# Thomas.net
KiCad netlist of a schematic drawn in EAGLE
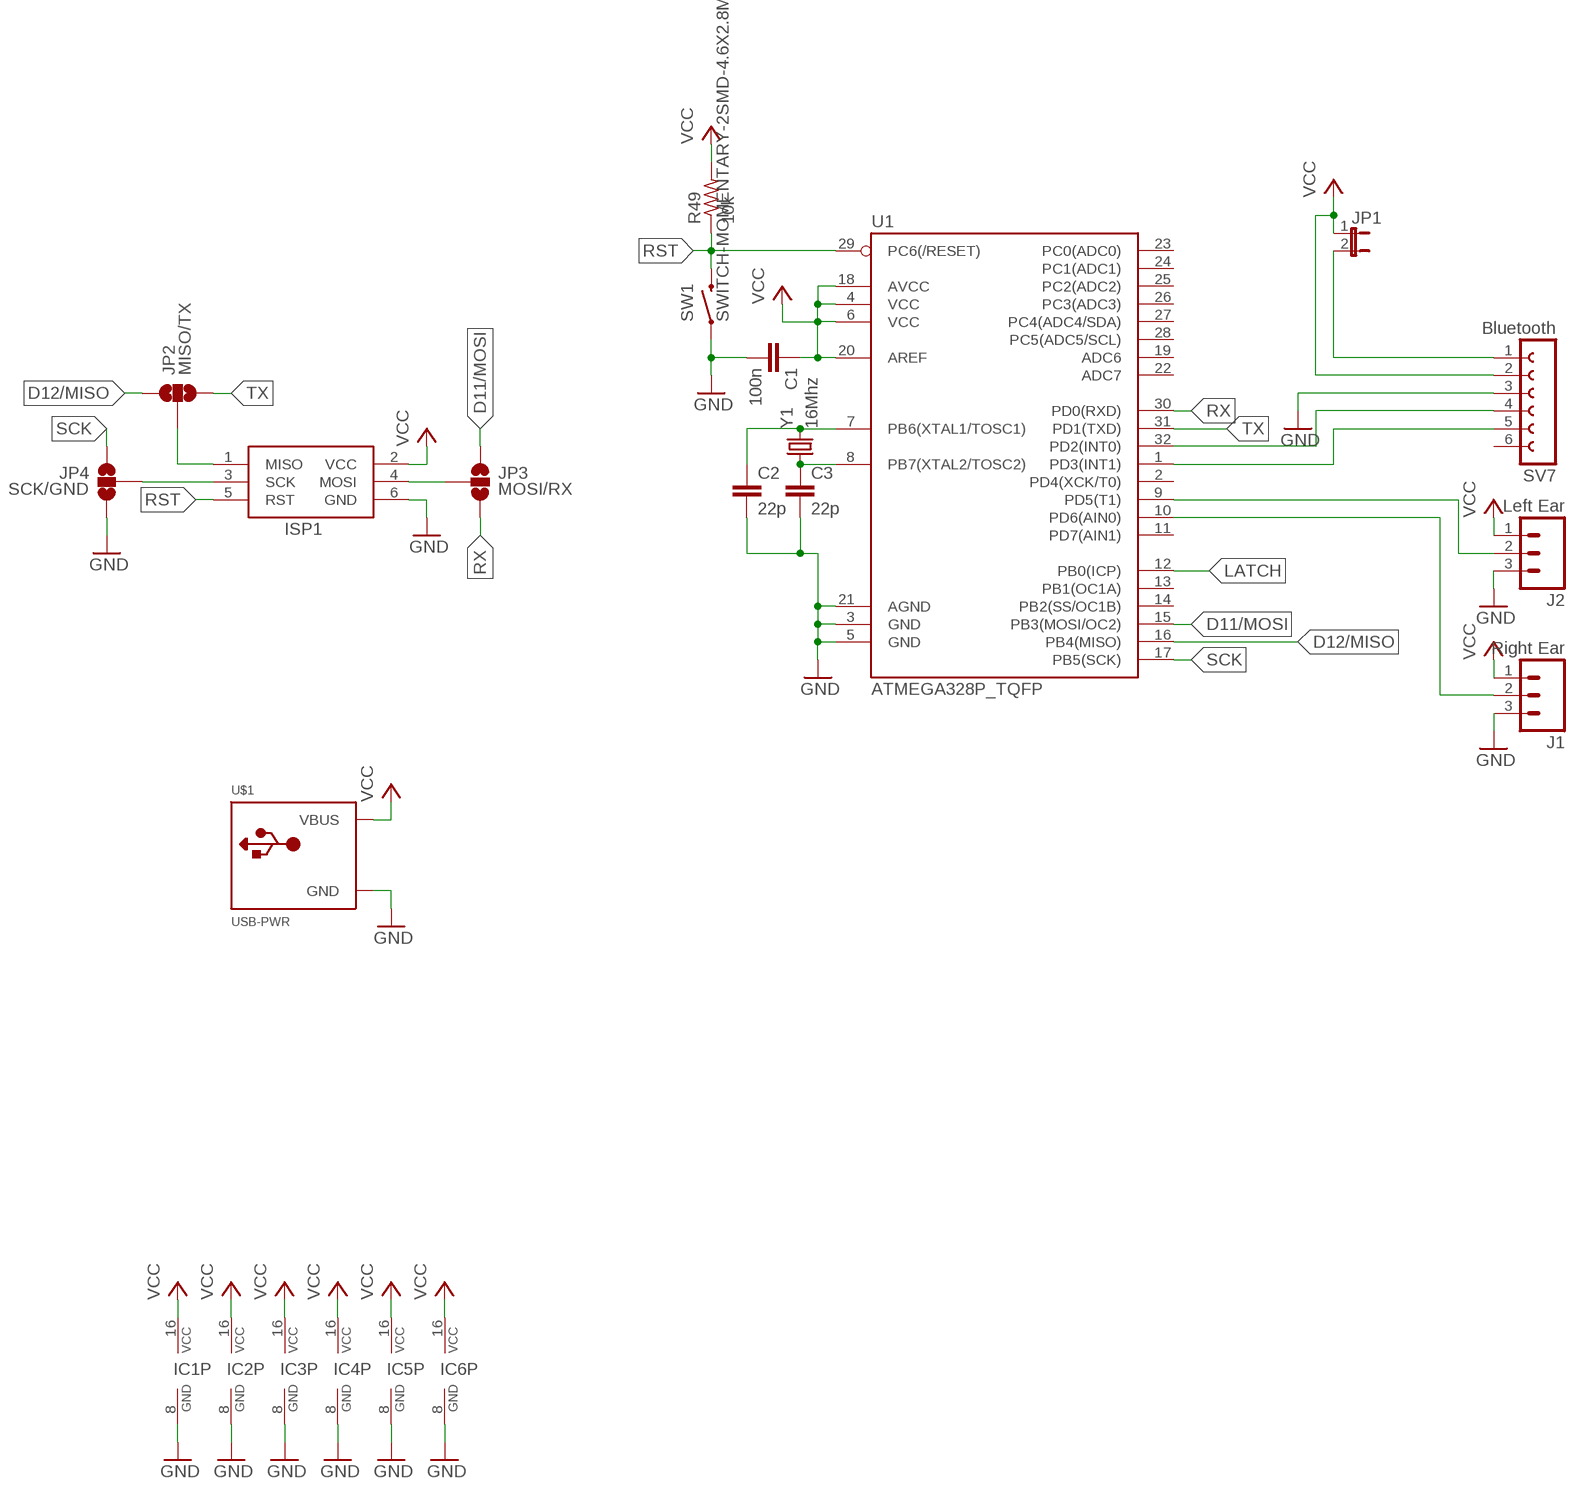
[diagram p0: schematic, sheet 1, part 1 of 2]
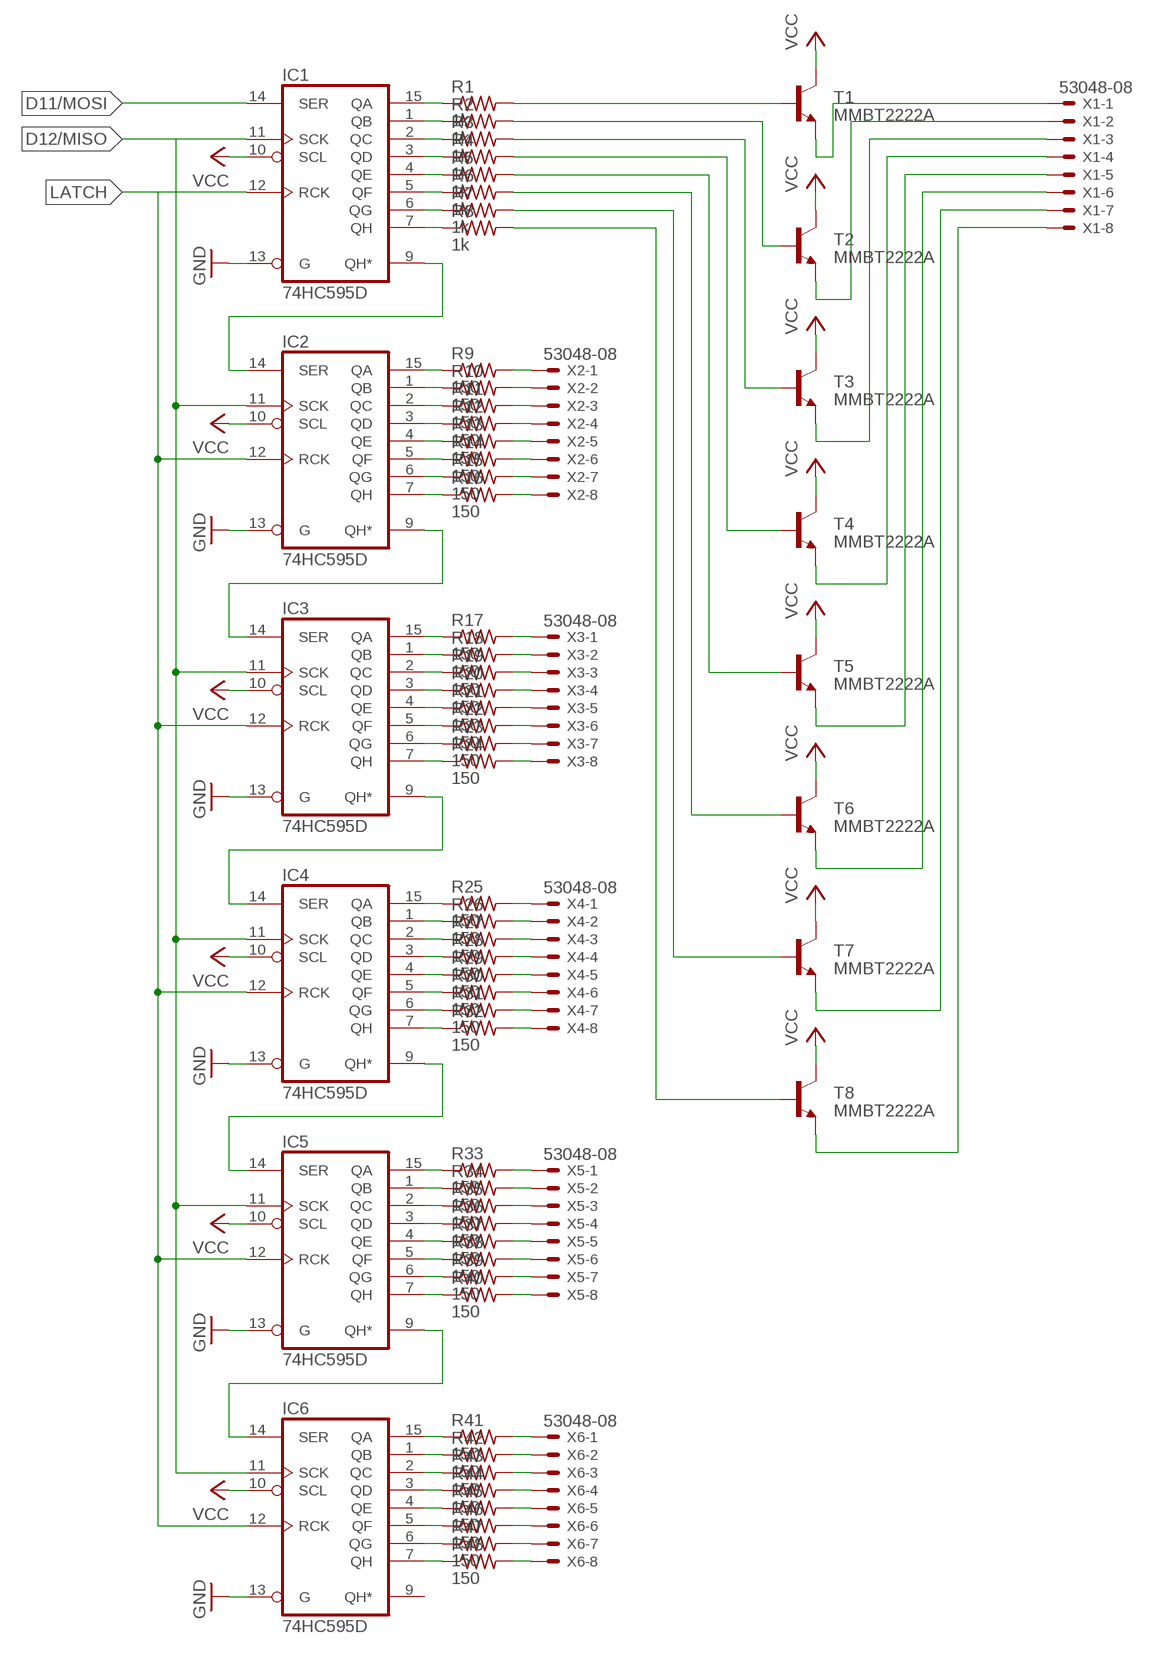
[diagram p1: schematic, sheet 1, part 2 of 2]

(export (version "E")
  (design (tool "Eeschema 10.0.6"))
  (components
    (comp (ref "C1")
      (value "100n")
      (footprint "eagle-import:C0805K")
      (libsource (lib "eagle-import") (part "C-EUC0805K"))
    )
    (comp (ref "C2")
      (value "22p")
      (footprint "eagle-import:C0805K")
      (libsource (lib "eagle-import") (part "C-EUC0805K"))
    )
    (comp (ref "C3")
      (value "22p")
      (footprint "eagle-import:C0805K")
      (libsource (lib "eagle-import") (part "C-EUC0805K"))
    )
    (comp (ref "IC1")
      (value "74HC595D")
      (footprint "eagle-import:SO16")
      (libsource (lib "eagle-import") (part "74595DHC"))
    )
    (comp (ref "IC2")
      (value "74HC595D")
      (footprint "eagle-import:SO16")
      (libsource (lib "eagle-import") (part "74595DHC"))
    )
    (comp (ref "IC3")
      (value "74HC595D")
      (footprint "eagle-import:SO16")
      (libsource (lib "eagle-import") (part "74595DHC"))
    )
    (comp (ref "IC4")
      (value "74HC595D")
      (footprint "eagle-import:SO16")
      (libsource (lib "eagle-import") (part "74595DHC"))
    )
    (comp (ref "IC5")
      (value "74HC595D")
      (footprint "eagle-import:SO16")
      (libsource (lib "eagle-import") (part "74595DHC"))
    )
    (comp (ref "IC6")
      (value "74HC595D")
      (footprint "eagle-import:SO16")
      (libsource (lib "eagle-import") (part "74595DHC"))
    )
    (comp (ref "ISP1")
      (value "AVRISP-6")
      (footprint "eagle-import:AVRISP")
      (libsource (lib "eagle-import") (part "AVRISP-6"))
    )
    (comp (ref "J1")
      (value "Right Ear")
      (footprint "eagle-import:1X03")
      (libsource (lib "eagle-import") (part "M03PTH"))
    )
    (comp (ref "J2")
      (value "Left Ear")
      (footprint "eagle-import:1X03")
      (libsource (lib "eagle-import") (part "M03PTH"))
    )
    (comp (ref "JP1")
      (value "JUMPER-2SMD-NC")
      (footprint "eagle-import:SJ_2S")
      (libsource (lib "eagle-import") (part "JUMPER-2SMD-NC"))
    )
    (comp (ref "JP2")
      (value "MISO/TX")
      (footprint "eagle-import:PAD-JUMPER-3-NO_YES_SILK")
      (libsource (lib "eagle-import") (part "JUMPER-PAD-3-NOYES_SILK"))
    )
    (comp (ref "JP3")
      (value "MOSI/RX")
      (footprint "eagle-import:PAD-JUMPER-3-NO_YES_SILK")
      (libsource (lib "eagle-import") (part "JUMPER-PAD-3-NOYES_SILK"))
    )
    (comp (ref "JP4")
      (value "SCK/GND")
      (footprint "eagle-import:PAD-JUMPER-3-NO_YES_SILK")
      (libsource (lib "eagle-import") (part "JUMPER-PAD-3-NOYES_SILK"))
    )
    (comp (ref "R1")
      (value "1k")
      (footprint "eagle-import:R0805")
      (libsource (lib "eagle-import") (part "R-US_R0805"))
    )
    (comp (ref "R2")
      (value "1k")
      (footprint "eagle-import:R0805")
      (libsource (lib "eagle-import") (part "R-US_R0805"))
    )
    (comp (ref "R3")
      (value "1k")
      (footprint "eagle-import:R0805")
      (libsource (lib "eagle-import") (part "R-US_R0805"))
    )
    (comp (ref "R4")
      (value "1k")
      (footprint "eagle-import:R0805")
      (libsource (lib "eagle-import") (part "R-US_R0805"))
    )
    (comp (ref "R5")
      (value "1k")
      (footprint "eagle-import:R0805")
      (libsource (lib "eagle-import") (part "R-US_R0805"))
    )
    (comp (ref "R6")
      (value "1k")
      (footprint "eagle-import:R0805")
      (libsource (lib "eagle-import") (part "R-US_R0805"))
    )
    (comp (ref "R7")
      (value "1k")
      (footprint "eagle-import:R0805")
      (libsource (lib "eagle-import") (part "R-US_R0805"))
    )
    (comp (ref "R8")
      (value "1k")
      (footprint "eagle-import:R0805")
      (libsource (lib "eagle-import") (part "R-US_R0805"))
    )
    (comp (ref "R9")
      (value "150")
      (footprint "eagle-import:R0805")
      (libsource (lib "eagle-import") (part "R-US_R0805"))
    )
    (comp (ref "R10")
      (value "150")
      (footprint "eagle-import:R0805")
      (libsource (lib "eagle-import") (part "R-US_R0805"))
    )
    (comp (ref "R11")
      (value "150")
      (footprint "eagle-import:R0805")
      (libsource (lib "eagle-import") (part "R-US_R0805"))
    )
    (comp (ref "R12")
      (value "150")
      (footprint "eagle-import:R0805")
      (libsource (lib "eagle-import") (part "R-US_R0805"))
    )
    (comp (ref "R13")
      (value "150")
      (footprint "eagle-import:R0805")
      (libsource (lib "eagle-import") (part "R-US_R0805"))
    )
    (comp (ref "R14")
      (value "150")
      (footprint "eagle-import:R0805")
      (libsource (lib "eagle-import") (part "R-US_R0805"))
    )
    (comp (ref "R15")
      (value "150")
      (footprint "eagle-import:R0805")
      (libsource (lib "eagle-import") (part "R-US_R0805"))
    )
    (comp (ref "R16")
      (value "150")
      (footprint "eagle-import:R0805")
      (libsource (lib "eagle-import") (part "R-US_R0805"))
    )
    (comp (ref "R17")
      (value "150")
      (footprint "eagle-import:R0805")
      (libsource (lib "eagle-import") (part "R-US_R0805"))
    )
    (comp (ref "R18")
      (value "150")
      (footprint "eagle-import:R0805")
      (libsource (lib "eagle-import") (part "R-US_R0805"))
    )
    (comp (ref "R19")
      (value "150")
      (footprint "eagle-import:R0805")
      (libsource (lib "eagle-import") (part "R-US_R0805"))
    )
    (comp (ref "R20")
      (value "150")
      (footprint "eagle-import:R0805")
      (libsource (lib "eagle-import") (part "R-US_R0805"))
    )
    (comp (ref "R21")
      (value "150")
      (footprint "eagle-import:R0805")
      (libsource (lib "eagle-import") (part "R-US_R0805"))
    )
    (comp (ref "R22")
      (value "150")
      (footprint "eagle-import:R0805")
      (libsource (lib "eagle-import") (part "R-US_R0805"))
    )
    (comp (ref "R23")
      (value "150")
      (footprint "eagle-import:R0805")
      (libsource (lib "eagle-import") (part "R-US_R0805"))
    )
    (comp (ref "R24")
      (value "150")
      (footprint "eagle-import:R0805")
      (libsource (lib "eagle-import") (part "R-US_R0805"))
    )
    (comp (ref "R25")
      (value "150")
      (footprint "eagle-import:R0805")
      (libsource (lib "eagle-import") (part "R-US_R0805"))
    )
    (comp (ref "R26")
      (value "150")
      (footprint "eagle-import:R0805")
      (libsource (lib "eagle-import") (part "R-US_R0805"))
    )
    (comp (ref "R27")
      (value "150")
      (footprint "eagle-import:R0805")
      (libsource (lib "eagle-import") (part "R-US_R0805"))
    )
    (comp (ref "R28")
      (value "150")
      (footprint "eagle-import:R0805")
      (libsource (lib "eagle-import") (part "R-US_R0805"))
    )
    (comp (ref "R29")
      (value "150")
      (footprint "eagle-import:R0805")
      (libsource (lib "eagle-import") (part "R-US_R0805"))
    )
    (comp (ref "R30")
      (value "150")
      (footprint "eagle-import:R0805")
      (libsource (lib "eagle-import") (part "R-US_R0805"))
    )
    (comp (ref "R31")
      (value "150")
      (footprint "eagle-import:R0805")
      (libsource (lib "eagle-import") (part "R-US_R0805"))
    )
    (comp (ref "R32")
      (value "150")
      (footprint "eagle-import:R0805")
      (libsource (lib "eagle-import") (part "R-US_R0805"))
    )
    (comp (ref "R33")
      (value "150")
      (footprint "eagle-import:R0805")
      (libsource (lib "eagle-import") (part "R-US_R0805"))
    )
    (comp (ref "R34")
      (value "150")
      (footprint "eagle-import:R0805")
      (libsource (lib "eagle-import") (part "R-US_R0805"))
    )
    (comp (ref "R35")
      (value "150")
      (footprint "eagle-import:R0805")
      (libsource (lib "eagle-import") (part "R-US_R0805"))
    )
    (comp (ref "R36")
      (value "150")
      (footprint "eagle-import:R0805")
      (libsource (lib "eagle-import") (part "R-US_R0805"))
    )
    (comp (ref "R37")
      (value "150")
      (footprint "eagle-import:R0805")
      (libsource (lib "eagle-import") (part "R-US_R0805"))
    )
    (comp (ref "R38")
      (value "150")
      (footprint "eagle-import:R0805")
      (libsource (lib "eagle-import") (part "R-US_R0805"))
    )
    (comp (ref "R39")
      (value "150")
      (footprint "eagle-import:R0805")
      (libsource (lib "eagle-import") (part "R-US_R0805"))
    )
    (comp (ref "R40")
      (value "150")
      (footprint "eagle-import:R0805")
      (libsource (lib "eagle-import") (part "R-US_R0805"))
    )
    (comp (ref "R41")
      (value "150")
      (footprint "eagle-import:R0805")
      (libsource (lib "eagle-import") (part "R-US_R0805"))
    )
    (comp (ref "R42")
      (value "150")
      (footprint "eagle-import:R0805")
      (libsource (lib "eagle-import") (part "R-US_R0805"))
    )
    (comp (ref "R43")
      (value "150")
      (footprint "eagle-import:R0805")
      (libsource (lib "eagle-import") (part "R-US_R0805"))
    )
    (comp (ref "R44")
      (value "150")
      (footprint "eagle-import:R0805")
      (libsource (lib "eagle-import") (part "R-US_R0805"))
    )
    (comp (ref "R45")
      (value "150")
      (footprint "eagle-import:R0805")
      (libsource (lib "eagle-import") (part "R-US_R0805"))
    )
    (comp (ref "R46")
      (value "150")
      (footprint "eagle-import:R0805")
      (libsource (lib "eagle-import") (part "R-US_R0805"))
    )
    (comp (ref "R47")
      (value "150")
      (footprint "eagle-import:R0805")
      (libsource (lib "eagle-import") (part "R-US_R0805"))
    )
    (comp (ref "R48")
      (value "150")
      (footprint "eagle-import:R0805")
      (libsource (lib "eagle-import") (part "R-US_R0805"))
    )
    (comp (ref "R49")
      (value "10k")
      (footprint "eagle-import:R0805")
      (libsource (lib "eagle-import") (part "R-US_R0805"))
    )
    (comp (ref "SV7")
      (value "Bluetooth")
      (footprint "eagle-import:FE06")
      (libsource (lib "eagle-import") (part "FE06-1"))
    )
    (comp (ref "SW1")
      (value "SWITCH-MOMENTARY-2SMD-4.6X2.8MM")
      (footprint "eagle-import:TACTILE_SWITCH_SMD_4.6X2.8MM")
      (libsource (lib "eagle-import") (part "SWITCH-MOMENTARY-2SMD-4.6X2.8MM"))
    )
    (comp (ref "T1")
      (value "MMBT2222A")
      (footprint "eagle-import:SOT23-3")
      (libsource (lib "eagle-import") (part "TRANSISTOR_NPNMMBT2222A"))
    )
    (comp (ref "T2")
      (value "MMBT2222A")
      (footprint "eagle-import:SOT23-3")
      (libsource (lib "eagle-import") (part "TRANSISTOR_NPNMMBT2222A"))
    )
    (comp (ref "T3")
      (value "MMBT2222A")
      (footprint "eagle-import:SOT23-3")
      (libsource (lib "eagle-import") (part "TRANSISTOR_NPNMMBT2222A"))
    )
    (comp (ref "T4")
      (value "MMBT2222A")
      (footprint "eagle-import:SOT23-3")
      (libsource (lib "eagle-import") (part "TRANSISTOR_NPNMMBT2222A"))
    )
    (comp (ref "T5")
      (value "MMBT2222A")
      (footprint "eagle-import:SOT23-3")
      (libsource (lib "eagle-import") (part "TRANSISTOR_NPNMMBT2222A"))
    )
    (comp (ref "T6")
      (value "MMBT2222A")
      (footprint "eagle-import:SOT23-3")
      (libsource (lib "eagle-import") (part "TRANSISTOR_NPNMMBT2222A"))
    )
    (comp (ref "T7")
      (value "MMBT2222A")
      (footprint "eagle-import:SOT23-3")
      (libsource (lib "eagle-import") (part "TRANSISTOR_NPNMMBT2222A"))
    )
    (comp (ref "T8")
      (value "MMBT2222A")
      (footprint "eagle-import:SOT23-3")
      (libsource (lib "eagle-import") (part "TRANSISTOR_NPNMMBT2222A"))
    )
    (comp (ref "U$1")
      (value "USB-PWR")
      (footprint "eagle-import:USB-MINIB-THM-MOLEX-PWRONLY")
      (libsource (lib "eagle-import") (part "USB-PWR"))
    )
    (comp (ref "U1")
      (value "ATMEGA328P_TQFP")
      (footprint "eagle-import:TQFP32-08")
      (libsource (lib "eagle-import") (part "ATMEGA328P_TQFP"))
    )
    (comp (ref "X1")
      (value "53048-08")
      (footprint "eagle-import:53048-08")
      (fields (field (name "MF") "WALDOM/MOLEX") (field (name "MPN") "53048-0810"))
      (libsource (lib "eagle-import") (part "53?-08048"))
    )
    (comp (ref "X2")
      (value "53048-08")
      (footprint "eagle-import:53048-08")
      (fields (field (name "MF") "WALDOM/MOLEX") (field (name "MPN") "53048-0810"))
      (libsource (lib "eagle-import") (part "53?-08048"))
    )
    (comp (ref "X3")
      (value "53048-08")
      (footprint "eagle-import:53048-08")
      (fields (field (name "MF") "WALDOM/MOLEX") (field (name "MPN") "53048-0810"))
      (libsource (lib "eagle-import") (part "53?-08048"))
    )
    (comp (ref "X4")
      (value "53048-08")
      (footprint "eagle-import:53048-08")
      (fields (field (name "MF") "WALDOM/MOLEX") (field (name "MPN") "53048-0810"))
      (libsource (lib "eagle-import") (part "53?-08048"))
    )
    (comp (ref "X5")
      (value "53048-08")
      (footprint "eagle-import:53048-08")
      (fields (field (name "MF") "WALDOM/MOLEX") (field (name "MPN") "53048-0810"))
      (libsource (lib "eagle-import") (part "53?-08048"))
    )
    (comp (ref "X6")
      (value "53048-08")
      (footprint "eagle-import:53048-08")
      (fields (field (name "MF") "WALDOM/MOLEX") (field (name "MPN") "53048-0810"))
      (libsource (lib "eagle-import") (part "53?-08048"))
    )
    (comp (ref "Y1")
      (value "16Mhz")
      (footprint "eagle-import:CRYSTAL-SMD-3.2X1.5MM")
      (libsource (lib "eagle-import") (part "CRYSTAL3.2X1.5MM"))
    )
  )
  (nets
    (net (code "1") (name "D11{slash}MOSI") (class "Default")
      (node (ref "IC1") (pin "14") (pinfunction "SER_14") (pintype "input"))
      (node (ref "JP3") (pin "1") (pinfunction "1_1") (pintype "passive"))
      (node (ref "U1") (pin "15") (pinfunction "PB3(MOSI/OC2)_15") (pintype "bidirectional"))
    )
    (net (code "2") (name "D12{slash}MISO") (class "Default")
      (node (ref "IC1") (pin "11") (pinfunction "SCK_11") (pintype "input"))
      (node (ref "IC2") (pin "11") (pinfunction "SCK_11") (pintype "input"))
      (node (ref "IC3") (pin "11") (pinfunction "SCK_11") (pintype "input"))
      (node (ref "IC4") (pin "11") (pinfunction "SCK_11") (pintype "input"))
      (node (ref "IC5") (pin "11") (pinfunction "SCK_11") (pintype "input"))
      (node (ref "IC6") (pin "11") (pinfunction "SCK_11") (pintype "input"))
      (node (ref "JP2") (pin "1") (pinfunction "1_1") (pintype "passive"))
      (node (ref "U1") (pin "16") (pinfunction "PB4(MISO)_16") (pintype "bidirectional"))
    )
    (net (code "3") (name "GND") (class "Default")
      (node (ref "C1") (pin "2") (pinfunction "2_2") (pintype "passive"))
      (node (ref "C2") (pin "2") (pinfunction "2_2") (pintype "passive"))
      (node (ref "C3") (pin "2") (pinfunction "2_2") (pintype "passive"))
      (node (ref "IC1") (pin "13") (pinfunction "G_13") (pintype "input"))
      (node (ref "IC1") (pin "8") (pinfunction "GND_8") (pintype "power_in"))
      (node (ref "IC2") (pin "13") (pinfunction "G_13") (pintype "input"))
      (node (ref "IC2") (pin "8") (pinfunction "GND_8") (pintype "power_in"))
      (node (ref "IC3") (pin "13") (pinfunction "G_13") (pintype "input"))
      (node (ref "IC3") (pin "8") (pinfunction "GND_8") (pintype "power_in"))
      (node (ref "IC4") (pin "13") (pinfunction "G_13") (pintype "input"))
      (node (ref "IC4") (pin "8") (pinfunction "GND_8") (pintype "power_in"))
      (node (ref "IC5") (pin "13") (pinfunction "G_13") (pintype "input"))
      (node (ref "IC5") (pin "8") (pinfunction "GND_8") (pintype "power_in"))
      (node (ref "IC6") (pin "13") (pinfunction "G_13") (pintype "input"))
      (node (ref "IC6") (pin "8") (pinfunction "GND_8") (pintype "power_in"))
      (node (ref "ISP1") (pin "6") (pinfunction "GND_6") (pintype "power_in"))
      (node (ref "J1") (pin "3") (pinfunction "3_3") (pintype "passive"))
      (node (ref "J2") (pin "3") (pinfunction "3_3") (pintype "passive"))
      (node (ref "JP4") (pin "3") (pinfunction "3_3") (pintype "passive"))
      (node (ref "SV7") (pin "3") (pinfunction "3_3") (pintype "passive"))
      (node (ref "SW1") (pin "1") (pinfunction "1_1") (pintype "passive"))
      (node (ref "SW1") (pin "2") (pinfunction "1_2") (pintype "passive"))
      (node (ref "U$1") (pin "GND") (pinfunction "GND_GND") (pintype "power_in"))
      (node (ref "U1") (pin "21") (pinfunction "AGND_21") (pintype "bidirectional"))
      (node (ref "U1") (pin "3") (pinfunction "GND_3") (pintype "bidirectional"))
      (node (ref "U1") (pin "5") (pinfunction "GND_5") (pintype "bidirectional"))
    )
    (net (code "4") (name "LATCH") (class "Default")
      (node (ref "IC1") (pin "12") (pinfunction "RCK_12") (pintype "input"))
      (node (ref "IC2") (pin "12") (pinfunction "RCK_12") (pintype "input"))
      (node (ref "IC3") (pin "12") (pinfunction "RCK_12") (pintype "input"))
      (node (ref "IC4") (pin "12") (pinfunction "RCK_12") (pintype "input"))
      (node (ref "IC5") (pin "12") (pinfunction "RCK_12") (pintype "input"))
      (node (ref "IC6") (pin "12") (pinfunction "RCK_12") (pintype "input"))
      (node (ref "U1") (pin "12") (pinfunction "PB0(ICP)_12") (pintype "bidirectional"))
    )
    (net (code "5") (name "Net-(IC1A-QA)") (class "Default")
      (node (ref "IC1") (pin "15") (pinfunction "QA_15") (pintype "tri_state"))
      (node (ref "R1") (pin "1") (pinfunction "1_1") (pintype "passive"))
    )
    (net (code "6") (name "Net-(IC1A-QB)") (class "Default")
      (node (ref "IC1") (pin "1") (pinfunction "QB_1") (pintype "tri_state"))
      (node (ref "R2") (pin "1") (pinfunction "1_1") (pintype "passive"))
    )
    (net (code "7") (name "Net-(IC1A-QC)") (class "Default")
      (node (ref "IC1") (pin "2") (pinfunction "QC_2") (pintype "tri_state"))
      (node (ref "R3") (pin "1") (pinfunction "1_1") (pintype "passive"))
    )
    (net (code "8") (name "Net-(IC1A-QD)") (class "Default")
      (node (ref "IC1") (pin "3") (pinfunction "QD_3") (pintype "tri_state"))
      (node (ref "R4") (pin "1") (pinfunction "1_1") (pintype "passive"))
    )
    (net (code "9") (name "Net-(IC1A-QE)") (class "Default")
      (node (ref "IC1") (pin "4") (pinfunction "QE_4") (pintype "tri_state"))
      (node (ref "R5") (pin "1") (pinfunction "1_1") (pintype "passive"))
    )
    (net (code "10") (name "Net-(IC1A-QF)") (class "Default")
      (node (ref "IC1") (pin "5") (pinfunction "QF_5") (pintype "tri_state"))
      (node (ref "R6") (pin "1") (pinfunction "1_1") (pintype "passive"))
    )
    (net (code "11") (name "Net-(IC1A-QG)") (class "Default")
      (node (ref "IC1") (pin "6") (pinfunction "QG_6") (pintype "tri_state"))
      (node (ref "R7") (pin "1") (pinfunction "1_1") (pintype "passive"))
    )
    (net (code "12") (name "Net-(IC1A-QH)") (class "Default")
      (node (ref "IC1") (pin "7") (pinfunction "QH_7") (pintype "tri_state"))
      (node (ref "R8") (pin "1") (pinfunction "1_1") (pintype "passive"))
    )
    (net (code "13") (name "Net-(IC1A-QH*)") (class "Default")
      (node (ref "IC1") (pin "9") (pinfunction "QH*_9") (pintype "tri_state"))
      (node (ref "IC2") (pin "14") (pinfunction "SER_14") (pintype "input"))
    )
    (net (code "14") (name "Net-(IC2A-QA)") (class "Default")
      (node (ref "IC2") (pin "15") (pinfunction "QA_15") (pintype "tri_state"))
      (node (ref "R9") (pin "1") (pinfunction "1_1") (pintype "passive"))
    )
    (net (code "15") (name "Net-(IC2A-QB)") (class "Default")
      (node (ref "IC2") (pin "1") (pinfunction "QB_1") (pintype "tri_state"))
      (node (ref "R10") (pin "1") (pinfunction "1_1") (pintype "passive"))
    )
    (net (code "16") (name "Net-(IC2A-QC)") (class "Default")
      (node (ref "IC2") (pin "2") (pinfunction "QC_2") (pintype "tri_state"))
      (node (ref "R11") (pin "1") (pinfunction "1_1") (pintype "passive"))
    )
    (net (code "17") (name "Net-(IC2A-QD)") (class "Default")
      (node (ref "IC2") (pin "3") (pinfunction "QD_3") (pintype "tri_state"))
      (node (ref "R12") (pin "1") (pinfunction "1_1") (pintype "passive"))
    )
    (net (code "18") (name "Net-(IC2A-QE)") (class "Default")
      (node (ref "IC2") (pin "4") (pinfunction "QE_4") (pintype "tri_state"))
      (node (ref "R13") (pin "1") (pinfunction "1_1") (pintype "passive"))
    )
    (net (code "19") (name "Net-(IC2A-QF)") (class "Default")
      (node (ref "IC2") (pin "5") (pinfunction "QF_5") (pintype "tri_state"))
      (node (ref "R14") (pin "1") (pinfunction "1_1") (pintype "passive"))
    )
    (net (code "20") (name "Net-(IC2A-QG)") (class "Default")
      (node (ref "IC2") (pin "6") (pinfunction "QG_6") (pintype "tri_state"))
      (node (ref "R15") (pin "1") (pinfunction "1_1") (pintype "passive"))
    )
    (net (code "21") (name "Net-(IC2A-QH)") (class "Default")
      (node (ref "IC2") (pin "7") (pinfunction "QH_7") (pintype "tri_state"))
      (node (ref "R16") (pin "1") (pinfunction "1_1") (pintype "passive"))
    )
    (net (code "22") (name "Net-(IC2A-QH*)") (class "Default")
      (node (ref "IC2") (pin "9") (pinfunction "QH*_9") (pintype "tri_state"))
      (node (ref "IC3") (pin "14") (pinfunction "SER_14") (pintype "input"))
    )
    (net (code "23") (name "Net-(IC3A-QA)") (class "Default")
      (node (ref "IC3") (pin "15") (pinfunction "QA_15") (pintype "tri_state"))
      (node (ref "R17") (pin "1") (pinfunction "1_1") (pintype "passive"))
    )
    (net (code "24") (name "Net-(IC3A-QB)") (class "Default")
      (node (ref "IC3") (pin "1") (pinfunction "QB_1") (pintype "tri_state"))
      (node (ref "R18") (pin "1") (pinfunction "1_1") (pintype "passive"))
    )
    (net (code "25") (name "Net-(IC3A-QC)") (class "Default")
      (node (ref "IC3") (pin "2") (pinfunction "QC_2") (pintype "tri_state"))
      (node (ref "R19") (pin "1") (pinfunction "1_1") (pintype "passive"))
    )
    (net (code "26") (name "Net-(IC3A-QD)") (class "Default")
      (node (ref "IC3") (pin "3") (pinfunction "QD_3") (pintype "tri_state"))
      (node (ref "R20") (pin "1") (pinfunction "1_1") (pintype "passive"))
    )
    (net (code "27") (name "Net-(IC3A-QE)") (class "Default")
      (node (ref "IC3") (pin "4") (pinfunction "QE_4") (pintype "tri_state"))
      (node (ref "R21") (pin "1") (pinfunction "1_1") (pintype "passive"))
    )
    (net (code "28") (name "Net-(IC3A-QF)") (class "Default")
      (node (ref "IC3") (pin "5") (pinfunction "QF_5") (pintype "tri_state"))
      (node (ref "R22") (pin "1") (pinfunction "1_1") (pintype "passive"))
    )
    (net (code "29") (name "Net-(IC3A-QG)") (class "Default")
      (node (ref "IC3") (pin "6") (pinfunction "QG_6") (pintype "tri_state"))
      (node (ref "R23") (pin "1") (pinfunction "1_1") (pintype "passive"))
    )
    (net (code "30") (name "Net-(IC3A-QH)") (class "Default")
      (node (ref "IC3") (pin "7") (pinfunction "QH_7") (pintype "tri_state"))
      (node (ref "R24") (pin "1") (pinfunction "1_1") (pintype "passive"))
    )
    (net (code "31") (name "Net-(IC3A-QH*)") (class "Default")
      (node (ref "IC3") (pin "9") (pinfunction "QH*_9") (pintype "tri_state"))
      (node (ref "IC4") (pin "14") (pinfunction "SER_14") (pintype "input"))
    )
    (net (code "32") (name "Net-(IC4A-QA)") (class "Default")
      (node (ref "IC4") (pin "15") (pinfunction "QA_15") (pintype "tri_state"))
      (node (ref "R25") (pin "1") (pinfunction "1_1") (pintype "passive"))
    )
    (net (code "33") (name "Net-(IC4A-QB)") (class "Default")
      (node (ref "IC4") (pin "1") (pinfunction "QB_1") (pintype "tri_state"))
      (node (ref "R26") (pin "1") (pinfunction "1_1") (pintype "passive"))
    )
    (net (code "34") (name "Net-(IC4A-QC)") (class "Default")
      (node (ref "IC4") (pin "2") (pinfunction "QC_2") (pintype "tri_state"))
      (node (ref "R27") (pin "1") (pinfunction "1_1") (pintype "passive"))
    )
    (net (code "35") (name "Net-(IC4A-QD)") (class "Default")
      (node (ref "IC4") (pin "3") (pinfunction "QD_3") (pintype "tri_state"))
      (node (ref "R28") (pin "1") (pinfunction "1_1") (pintype "passive"))
    )
    (net (code "36") (name "Net-(IC4A-QE)") (class "Default")
      (node (ref "IC4") (pin "4") (pinfunction "QE_4") (pintype "tri_state"))
      (node (ref "R29") (pin "1") (pinfunction "1_1") (pintype "passive"))
    )
    (net (code "37") (name "Net-(IC4A-QF)") (class "Default")
      (node (ref "IC4") (pin "5") (pinfunction "QF_5") (pintype "tri_state"))
      (node (ref "R30") (pin "1") (pinfunction "1_1") (pintype "passive"))
    )
    (net (code "38") (name "Net-(IC4A-QG)") (class "Default")
      (node (ref "IC4") (pin "6") (pinfunction "QG_6") (pintype "tri_state"))
      (node (ref "R31") (pin "1") (pinfunction "1_1") (pintype "passive"))
    )
    (net (code "39") (name "Net-(IC4A-QH)") (class "Default")
      (node (ref "IC4") (pin "7") (pinfunction "QH_7") (pintype "tri_state"))
      (node (ref "R32") (pin "1") (pinfunction "1_1") (pintype "passive"))
    )
    (net (code "40") (name "Net-(IC4A-QH*)") (class "Default")
      (node (ref "IC4") (pin "9") (pinfunction "QH*_9") (pintype "tri_state"))
      (node (ref "IC5") (pin "14") (pinfunction "SER_14") (pintype "input"))
    )
    (net (code "41") (name "Net-(IC5A-QA)") (class "Default")
      (node (ref "IC5") (pin "15") (pinfunction "QA_15") (pintype "tri_state"))
      (node (ref "R33") (pin "1") (pinfunction "1_1") (pintype "passive"))
    )
    (net (code "42") (name "Net-(IC5A-QB)") (class "Default")
      (node (ref "IC5") (pin "1") (pinfunction "QB_1") (pintype "tri_state"))
      (node (ref "R34") (pin "1") (pinfunction "1_1") (pintype "passive"))
    )
    (net (code "43") (name "Net-(IC5A-QC)") (class "Default")
      (node (ref "IC5") (pin "2") (pinfunction "QC_2") (pintype "tri_state"))
      (node (ref "R35") (pin "1") (pinfunction "1_1") (pintype "passive"))
    )
    (net (code "44") (name "Net-(IC5A-QD)") (class "Default")
      (node (ref "IC5") (pin "3") (pinfunction "QD_3") (pintype "tri_state"))
      (node (ref "R36") (pin "1") (pinfunction "1_1") (pintype "passive"))
    )
    (net (code "45") (name "Net-(IC5A-QE)") (class "Default")
      (node (ref "IC5") (pin "4") (pinfunction "QE_4") (pintype "tri_state"))
      (node (ref "R37") (pin "1") (pinfunction "1_1") (pintype "passive"))
    )
    (net (code "46") (name "Net-(IC5A-QF)") (class "Default")
      (node (ref "IC5") (pin "5") (pinfunction "QF_5") (pintype "tri_state"))
      (node (ref "R38") (pin "1") (pinfunction "1_1") (pintype "passive"))
    )
    (net (code "47") (name "Net-(IC5A-QG)") (class "Default")
      (node (ref "IC5") (pin "6") (pinfunction "QG_6") (pintype "tri_state"))
      (node (ref "R39") (pin "1") (pinfunction "1_1") (pintype "passive"))
    )
    (net (code "48") (name "Net-(IC5A-QH)") (class "Default")
      (node (ref "IC5") (pin "7") (pinfunction "QH_7") (pintype "tri_state"))
      (node (ref "R40") (pin "1") (pinfunction "1_1") (pintype "passive"))
    )
    (net (code "49") (name "Net-(IC5A-QH*)") (class "Default")
      (node (ref "IC5") (pin "9") (pinfunction "QH*_9") (pintype "tri_state"))
      (node (ref "IC6") (pin "14") (pinfunction "SER_14") (pintype "input"))
    )
    (net (code "50") (name "Net-(IC6A-QA)") (class "Default")
      (node (ref "IC6") (pin "15") (pinfunction "QA_15") (pintype "tri_state"))
      (node (ref "R41") (pin "1") (pinfunction "1_1") (pintype "passive"))
    )
    (net (code "51") (name "Net-(IC6A-QB)") (class "Default")
      (node (ref "IC6") (pin "1") (pinfunction "QB_1") (pintype "tri_state"))
      (node (ref "R42") (pin "1") (pinfunction "1_1") (pintype "passive"))
    )
    (net (code "52") (name "Net-(IC6A-QC)") (class "Default")
      (node (ref "IC6") (pin "2") (pinfunction "QC_2") (pintype "tri_state"))
      (node (ref "R43") (pin "1") (pinfunction "1_1") (pintype "passive"))
    )
    (net (code "53") (name "Net-(IC6A-QD)") (class "Default")
      (node (ref "IC6") (pin "3") (pinfunction "QD_3") (pintype "tri_state"))
      (node (ref "R44") (pin "1") (pinfunction "1_1") (pintype "passive"))
    )
    (net (code "54") (name "Net-(IC6A-QE)") (class "Default")
      (node (ref "IC6") (pin "4") (pinfunction "QE_4") (pintype "tri_state"))
      (node (ref "R45") (pin "1") (pinfunction "1_1") (pintype "passive"))
    )
    (net (code "55") (name "Net-(IC6A-QF)") (class "Default")
      (node (ref "IC6") (pin "5") (pinfunction "QF_5") (pintype "tri_state"))
      (node (ref "R46") (pin "1") (pinfunction "1_1") (pintype "passive"))
    )
    (net (code "56") (name "Net-(IC6A-QG)") (class "Default")
      (node (ref "IC6") (pin "6") (pinfunction "QG_6") (pintype "tri_state"))
      (node (ref "R47") (pin "1") (pinfunction "1_1") (pintype "passive"))
    )
    (net (code "57") (name "Net-(IC6A-QH)") (class "Default")
      (node (ref "IC6") (pin "7") (pinfunction "QH_7") (pintype "tri_state"))
      (node (ref "R48") (pin "1") (pinfunction "1_1") (pintype "passive"))
    )
    (net (code "58") (name "Net-(ISP1-MISO)") (class "Default")
      (node (ref "ISP1") (pin "1") (pinfunction "MISO_1") (pintype "input"))
      (node (ref "JP2") (pin "2") (pinfunction "2_2") (pintype "passive"))
    )
    (net (code "59") (name "Net-(ISP1-MOSI)") (class "Default")
      (node (ref "ISP1") (pin "4") (pinfunction "MOSI_4") (pintype "output"))
      (node (ref "JP3") (pin "2") (pinfunction "2_2") (pintype "passive"))
    )
    (net (code "60") (name "Net-(ISP1-SCK)") (class "Default")
      (node (ref "ISP1") (pin "3") (pinfunction "SCK_3") (pintype "output"))
      (node (ref "JP4") (pin "2") (pinfunction "2_2") (pintype "passive"))
    )
    (net (code "61") (name "Net-(JP1-Pad2)") (class "Default")
      (node (ref "JP1") (pin "2") (pinfunction "2_2") (pintype "passive"))
      (node (ref "SV7") (pin "1") (pinfunction "1_1") (pintype "passive"))
    )
    (net (code "62") (name "Net-(T1-B)") (class "Default")
      (node (ref "R1") (pin "2") (pinfunction "2_2") (pintype "passive"))
      (node (ref "T1") (pin "1") (pinfunction "B_1") (pintype "passive"))
    )
    (net (code "63") (name "Net-(T1-E)") (class "Default")
      (node (ref "T1") (pin "2") (pinfunction "E_2") (pintype "passive"))
      (node (ref "X1") (pin "1") (pinfunction "S_1") (pintype "passive"))
    )
    (net (code "64") (name "Net-(T2-B)") (class "Default")
      (node (ref "R2") (pin "2") (pinfunction "2_2") (pintype "passive"))
      (node (ref "T2") (pin "1") (pinfunction "B_1") (pintype "passive"))
    )
    (net (code "65") (name "Net-(T2-E)") (class "Default")
      (node (ref "T2") (pin "2") (pinfunction "E_2") (pintype "passive"))
      (node (ref "X1") (pin "2") (pinfunction "S_2") (pintype "passive"))
    )
    (net (code "66") (name "Net-(T3-B)") (class "Default")
      (node (ref "R3") (pin "2") (pinfunction "2_2") (pintype "passive"))
      (node (ref "T3") (pin "1") (pinfunction "B_1") (pintype "passive"))
    )
    (net (code "67") (name "Net-(T3-E)") (class "Default")
      (node (ref "T3") (pin "2") (pinfunction "E_2") (pintype "passive"))
      (node (ref "X1") (pin "3") (pinfunction "S_3") (pintype "passive"))
    )
    (net (code "68") (name "Net-(T4-B)") (class "Default")
      (node (ref "R4") (pin "2") (pinfunction "2_2") (pintype "passive"))
      (node (ref "T4") (pin "1") (pinfunction "B_1") (pintype "passive"))
    )
    (net (code "69") (name "Net-(T4-E)") (class "Default")
      (node (ref "T4") (pin "2") (pinfunction "E_2") (pintype "passive"))
      (node (ref "X1") (pin "4") (pinfunction "S_4") (pintype "passive"))
    )
    (net (code "70") (name "Net-(T5-B)") (class "Default")
      (node (ref "R5") (pin "2") (pinfunction "2_2") (pintype "passive"))
      (node (ref "T5") (pin "1") (pinfunction "B_1") (pintype "passive"))
    )
    (net (code "71") (name "Net-(T5-E)") (class "Default")
      (node (ref "T5") (pin "2") (pinfunction "E_2") (pintype "passive"))
      (node (ref "X1") (pin "5") (pinfunction "S_5") (pintype "passive"))
    )
    (net (code "72") (name "Net-(T6-B)") (class "Default")
      (node (ref "R6") (pin "2") (pinfunction "2_2") (pintype "passive"))
      (node (ref "T6") (pin "1") (pinfunction "B_1") (pintype "passive"))
    )
    (net (code "73") (name "Net-(T6-E)") (class "Default")
      (node (ref "T6") (pin "2") (pinfunction "E_2") (pintype "passive"))
      (node (ref "X1") (pin "6") (pinfunction "S_6") (pintype "passive"))
    )
    (net (code "74") (name "Net-(T7-B)") (class "Default")
      (node (ref "R7") (pin "2") (pinfunction "2_2") (pintype "passive"))
      (node (ref "T7") (pin "1") (pinfunction "B_1") (pintype "passive"))
    )
    (net (code "75") (name "Net-(T7-E)") (class "Default")
      (node (ref "T7") (pin "2") (pinfunction "E_2") (pintype "passive"))
      (node (ref "X1") (pin "7") (pinfunction "S_7") (pintype "passive"))
    )
    (net (code "76") (name "Net-(T8-B)") (class "Default")
      (node (ref "R8") (pin "2") (pinfunction "2_2") (pintype "passive"))
      (node (ref "T8") (pin "1") (pinfunction "B_1") (pintype "passive"))
    )
    (net (code "77") (name "Net-(T8-E)") (class "Default")
      (node (ref "T8") (pin "2") (pinfunction "E_2") (pintype "passive"))
      (node (ref "X1") (pin "8") (pinfunction "S_8") (pintype "passive"))
    )
    (net (code "78") (name "Net-(U1-PB6(XTAL1{slash}TOSC1))") (class "Default")
      (node (ref "C2") (pin "1") (pinfunction "1_1") (pintype "passive"))
      (node (ref "U1") (pin "7") (pinfunction "PB6(XTAL1/TOSC1)_7") (pintype "bidirectional"))
      (node (ref "Y1") (pin "P$2") (pinfunction "2_P$2") (pintype "passive"))
    )
    (net (code "79") (name "Net-(U1-PB7(XTAL2{slash}TOSC2))") (class "Default")
      (node (ref "C3") (pin "1") (pinfunction "1_1") (pintype "passive"))
      (node (ref "U1") (pin "8") (pinfunction "PB7(XTAL2/TOSC2)_8") (pintype "bidirectional"))
      (node (ref "Y1") (pin "P$1") (pinfunction "1_P$1") (pintype "passive"))
    )
    (net (code "80") (name "Net-(U1-PD2(INT0))") (class "Default")
      (node (ref "SV7") (pin "4") (pinfunction "4_4") (pintype "passive"))
      (node (ref "U1") (pin "32") (pinfunction "PD2(INT0)_32") (pintype "bidirectional"))
    )
    (net (code "81") (name "Net-(U1-PD3(INT1))") (class "Default")
      (node (ref "SV7") (pin "5") (pinfunction "5_5") (pintype "passive"))
      (node (ref "U1") (pin "1") (pinfunction "PD3(INT1)_1") (pintype "bidirectional"))
    )
    (net (code "82") (name "Net-(U1-PD5(T1))") (class "Default")
      (node (ref "J2") (pin "2") (pinfunction "2_2") (pintype "passive"))
      (node (ref "U1") (pin "9") (pinfunction "PD5(T1)_9") (pintype "bidirectional"))
    )
    (net (code "83") (name "Net-(U1-PD6(AIN0))") (class "Default")
      (node (ref "J1") (pin "2") (pinfunction "2_2") (pintype "passive"))
      (node (ref "U1") (pin "10") (pinfunction "PD6(AIN0)_10") (pintype "bidirectional"))
    )
    (net (code "84") (name "Net-(X2A-S)") (class "Default")
      (node (ref "R9") (pin "2") (pinfunction "2_2") (pintype "passive"))
      (node (ref "X2") (pin "1") (pinfunction "S_1") (pintype "passive"))
    )
    (net (code "85") (name "Net-(X2B-S)") (class "Default")
      (node (ref "R10") (pin "2") (pinfunction "2_2") (pintype "passive"))
      (node (ref "X2") (pin "2") (pinfunction "S_2") (pintype "passive"))
    )
    (net (code "86") (name "Net-(X2C-S)") (class "Default")
      (node (ref "R11") (pin "2") (pinfunction "2_2") (pintype "passive"))
      (node (ref "X2") (pin "3") (pinfunction "S_3") (pintype "passive"))
    )
    (net (code "87") (name "Net-(X2D-S)") (class "Default")
      (node (ref "R12") (pin "2") (pinfunction "2_2") (pintype "passive"))
      (node (ref "X2") (pin "4") (pinfunction "S_4") (pintype "passive"))
    )
    (net (code "88") (name "Net-(X2E-S)") (class "Default")
      (node (ref "R13") (pin "2") (pinfunction "2_2") (pintype "passive"))
      (node (ref "X2") (pin "5") (pinfunction "S_5") (pintype "passive"))
    )
    (net (code "89") (name "Net-(X2F-S)") (class "Default")
      (node (ref "R14") (pin "2") (pinfunction "2_2") (pintype "passive"))
      (node (ref "X2") (pin "6") (pinfunction "S_6") (pintype "passive"))
    )
    (net (code "90") (name "Net-(X2G-S)") (class "Default")
      (node (ref "R15") (pin "2") (pinfunction "2_2") (pintype "passive"))
      (node (ref "X2") (pin "7") (pinfunction "S_7") (pintype "passive"))
    )
    (net (code "91") (name "Net-(X2H-S)") (class "Default")
      (node (ref "R16") (pin "2") (pinfunction "2_2") (pintype "passive"))
      (node (ref "X2") (pin "8") (pinfunction "S_8") (pintype "passive"))
    )
    (net (code "92") (name "Net-(X3A-S)") (class "Default")
      (node (ref "R17") (pin "2") (pinfunction "2_2") (pintype "passive"))
      (node (ref "X3") (pin "1") (pinfunction "S_1") (pintype "passive"))
    )
    (net (code "93") (name "Net-(X3B-S)") (class "Default")
      (node (ref "R18") (pin "2") (pinfunction "2_2") (pintype "passive"))
      (node (ref "X3") (pin "2") (pinfunction "S_2") (pintype "passive"))
    )
    (net (code "94") (name "Net-(X3C-S)") (class "Default")
      (node (ref "R19") (pin "2") (pinfunction "2_2") (pintype "passive"))
      (node (ref "X3") (pin "3") (pinfunction "S_3") (pintype "passive"))
    )
    (net (code "95") (name "Net-(X3D-S)") (class "Default")
      (node (ref "R20") (pin "2") (pinfunction "2_2") (pintype "passive"))
      (node (ref "X3") (pin "4") (pinfunction "S_4") (pintype "passive"))
    )
    (net (code "96") (name "Net-(X3E-S)") (class "Default")
      (node (ref "R21") (pin "2") (pinfunction "2_2") (pintype "passive"))
      (node (ref "X3") (pin "5") (pinfunction "S_5") (pintype "passive"))
    )
    (net (code "97") (name "Net-(X3F-S)") (class "Default")
      (node (ref "R22") (pin "2") (pinfunction "2_2") (pintype "passive"))
      (node (ref "X3") (pin "6") (pinfunction "S_6") (pintype "passive"))
    )
    (net (code "98") (name "Net-(X3G-S)") (class "Default")
      (node (ref "R23") (pin "2") (pinfunction "2_2") (pintype "passive"))
      (node (ref "X3") (pin "7") (pinfunction "S_7") (pintype "passive"))
    )
    (net (code "99") (name "Net-(X3H-S)") (class "Default")
      (node (ref "R24") (pin "2") (pinfunction "2_2") (pintype "passive"))
      (node (ref "X3") (pin "8") (pinfunction "S_8") (pintype "passive"))
    )
    (net (code "100") (name "Net-(X4A-S)") (class "Default")
      (node (ref "R25") (pin "2") (pinfunction "2_2") (pintype "passive"))
      (node (ref "X4") (pin "1") (pinfunction "S_1") (pintype "passive"))
    )
    (net (code "101") (name "Net-(X4B-S)") (class "Default")
      (node (ref "R26") (pin "2") (pinfunction "2_2") (pintype "passive"))
      (node (ref "X4") (pin "2") (pinfunction "S_2") (pintype "passive"))
    )
    (net (code "102") (name "Net-(X4C-S)") (class "Default")
      (node (ref "R27") (pin "2") (pinfunction "2_2") (pintype "passive"))
      (node (ref "X4") (pin "3") (pinfunction "S_3") (pintype "passive"))
    )
    (net (code "103") (name "Net-(X4D-S)") (class "Default")
      (node (ref "R28") (pin "2") (pinfunction "2_2") (pintype "passive"))
      (node (ref "X4") (pin "4") (pinfunction "S_4") (pintype "passive"))
    )
    (net (code "104") (name "Net-(X4E-S)") (class "Default")
      (node (ref "R29") (pin "2") (pinfunction "2_2") (pintype "passive"))
      (node (ref "X4") (pin "5") (pinfunction "S_5") (pintype "passive"))
    )
    (net (code "105") (name "Net-(X4F-S)") (class "Default")
      (node (ref "R30") (pin "2") (pinfunction "2_2") (pintype "passive"))
      (node (ref "X4") (pin "6") (pinfunction "S_6") (pintype "passive"))
    )
    (net (code "106") (name "Net-(X4G-S)") (class "Default")
      (node (ref "R31") (pin "2") (pinfunction "2_2") (pintype "passive"))
      (node (ref "X4") (pin "7") (pinfunction "S_7") (pintype "passive"))
    )
    (net (code "107") (name "Net-(X4H-S)") (class "Default")
      (node (ref "R32") (pin "2") (pinfunction "2_2") (pintype "passive"))
      (node (ref "X4") (pin "8") (pinfunction "S_8") (pintype "passive"))
    )
    (net (code "108") (name "Net-(X5A-S)") (class "Default")
      (node (ref "R33") (pin "2") (pinfunction "2_2") (pintype "passive"))
      (node (ref "X5") (pin "1") (pinfunction "S_1") (pintype "passive"))
    )
    (net (code "109") (name "Net-(X5B-S)") (class "Default")
      (node (ref "R34") (pin "2") (pinfunction "2_2") (pintype "passive"))
      (node (ref "X5") (pin "2") (pinfunction "S_2") (pintype "passive"))
    )
    (net (code "110") (name "Net-(X5C-S)") (class "Default")
      (node (ref "R35") (pin "2") (pinfunction "2_2") (pintype "passive"))
      (node (ref "X5") (pin "3") (pinfunction "S_3") (pintype "passive"))
    )
    (net (code "111") (name "Net-(X5D-S)") (class "Default")
      (node (ref "R36") (pin "2") (pinfunction "2_2") (pintype "passive"))
      (node (ref "X5") (pin "4") (pinfunction "S_4") (pintype "passive"))
    )
    (net (code "112") (name "Net-(X5E-S)") (class "Default")
      (node (ref "R37") (pin "2") (pinfunction "2_2") (pintype "passive"))
      (node (ref "X5") (pin "5") (pinfunction "S_5") (pintype "passive"))
    )
    (net (code "113") (name "Net-(X5F-S)") (class "Default")
      (node (ref "R38") (pin "2") (pinfunction "2_2") (pintype "passive"))
      (node (ref "X5") (pin "6") (pinfunction "S_6") (pintype "passive"))
    )
    (net (code "114") (name "Net-(X5G-S)") (class "Default")
      (node (ref "R39") (pin "2") (pinfunction "2_2") (pintype "passive"))
      (node (ref "X5") (pin "7") (pinfunction "S_7") (pintype "passive"))
    )
    (net (code "115") (name "Net-(X5H-S)") (class "Default")
      (node (ref "R40") (pin "2") (pinfunction "2_2") (pintype "passive"))
      (node (ref "X5") (pin "8") (pinfunction "S_8") (pintype "passive"))
    )
    (net (code "116") (name "Net-(X6A-S)") (class "Default")
      (node (ref "R41") (pin "2") (pinfunction "2_2") (pintype "passive"))
      (node (ref "X6") (pin "1") (pinfunction "S_1") (pintype "passive"))
    )
    (net (code "117") (name "Net-(X6B-S)") (class "Default")
      (node (ref "R42") (pin "2") (pinfunction "2_2") (pintype "passive"))
      (node (ref "X6") (pin "2") (pinfunction "S_2") (pintype "passive"))
    )
    (net (code "118") (name "Net-(X6C-S)") (class "Default")
      (node (ref "R43") (pin "2") (pinfunction "2_2") (pintype "passive"))
      (node (ref "X6") (pin "3") (pinfunction "S_3") (pintype "passive"))
    )
    (net (code "119") (name "Net-(X6D-S)") (class "Default")
      (node (ref "R44") (pin "2") (pinfunction "2_2") (pintype "passive"))
      (node (ref "X6") (pin "4") (pinfunction "S_4") (pintype "passive"))
    )
    (net (code "120") (name "Net-(X6E-S)") (class "Default")
      (node (ref "R45") (pin "2") (pinfunction "2_2") (pintype "passive"))
      (node (ref "X6") (pin "5") (pinfunction "S_5") (pintype "passive"))
    )
    (net (code "121") (name "Net-(X6F-S)") (class "Default")
      (node (ref "R46") (pin "2") (pinfunction "2_2") (pintype "passive"))
      (node (ref "X6") (pin "6") (pinfunction "S_6") (pintype "passive"))
    )
    (net (code "122") (name "Net-(X6G-S)") (class "Default")
      (node (ref "R47") (pin "2") (pinfunction "2_2") (pintype "passive"))
      (node (ref "X6") (pin "7") (pinfunction "S_7") (pintype "passive"))
    )
    (net (code "123") (name "Net-(X6H-S)") (class "Default")
      (node (ref "R48") (pin "2") (pinfunction "2_2") (pintype "passive"))
      (node (ref "X6") (pin "8") (pinfunction "S_8") (pintype "passive"))
    )
    (net (code "124") (name "RST") (class "Default")
      (node (ref "ISP1") (pin "5") (pinfunction "RST_5") (pintype "output"))
      (node (ref "R49") (pin "1") (pinfunction "1_1") (pintype "passive"))
      (node (ref "SW1") (pin "3") (pinfunction "2_3") (pintype "passive"))
      (node (ref "SW1") (pin "4") (pinfunction "2_4") (pintype "passive"))
      (node (ref "U1") (pin "29") (pinfunction "PC6(/RESET)_29") (pintype "bidirectional"))
    )
    (net (code "125") (name "RX") (class "Default")
      (node (ref "JP3") (pin "3") (pinfunction "3_3") (pintype "passive"))
      (node (ref "U1") (pin "30") (pinfunction "PD0(RXD)_30") (pintype "bidirectional"))
    )
    (net (code "126") (name "SCK") (class "Default")
      (node (ref "JP4") (pin "1") (pinfunction "1_1") (pintype "passive"))
      (node (ref "U1") (pin "17") (pinfunction "PB5(SCK)_17") (pintype "bidirectional"))
    )
    (net (code "127") (name "TX") (class "Default")
      (node (ref "JP2") (pin "3") (pinfunction "3_3") (pintype "passive"))
      (node (ref "U1") (pin "31") (pinfunction "PD1(TXD)_31") (pintype "bidirectional"))
    )
    (net (code "128") (name "VCC") (class "Default")
      (node (ref "C1") (pin "1") (pinfunction "1_1") (pintype "passive"))
      (node (ref "IC1") (pin "10") (pinfunction "SCL_10") (pintype "input"))
      (node (ref "IC1") (pin "16") (pinfunction "VCC_16") (pintype "power_in"))
      (node (ref "IC2") (pin "10") (pinfunction "SCL_10") (pintype "input"))
      (node (ref "IC2") (pin "16") (pinfunction "VCC_16") (pintype "power_in"))
      (node (ref "IC3") (pin "10") (pinfunction "SCL_10") (pintype "input"))
      (node (ref "IC3") (pin "16") (pinfunction "VCC_16") (pintype "power_in"))
      (node (ref "IC4") (pin "10") (pinfunction "SCL_10") (pintype "input"))
      (node (ref "IC4") (pin "16") (pinfunction "VCC_16") (pintype "power_in"))
      (node (ref "IC5") (pin "10") (pinfunction "SCL_10") (pintype "input"))
      (node (ref "IC5") (pin "16") (pinfunction "VCC_16") (pintype "power_in"))
      (node (ref "IC6") (pin "10") (pinfunction "SCL_10") (pintype "input"))
      (node (ref "IC6") (pin "16") (pinfunction "VCC_16") (pintype "power_in"))
      (node (ref "ISP1") (pin "2") (pinfunction "VCC_2") (pintype "power_in"))
      (node (ref "J1") (pin "1") (pinfunction "1_1") (pintype "passive"))
      (node (ref "J2") (pin "1") (pinfunction "1_1") (pintype "passive"))
      (node (ref "JP1") (pin "1") (pinfunction "1_1") (pintype "passive"))
      (node (ref "R49") (pin "2") (pinfunction "2_2") (pintype "passive"))
      (node (ref "SV7") (pin "2") (pinfunction "2_2") (pintype "passive"))
      (node (ref "T1") (pin "3") (pinfunction "C_3") (pintype "passive"))
      (node (ref "T2") (pin "3") (pinfunction "C_3") (pintype "passive"))
      (node (ref "T3") (pin "3") (pinfunction "C_3") (pintype "passive"))
      (node (ref "T4") (pin "3") (pinfunction "C_3") (pintype "passive"))
      (node (ref "T5") (pin "3") (pinfunction "C_3") (pintype "passive"))
      (node (ref "T6") (pin "3") (pinfunction "C_3") (pintype "passive"))
      (node (ref "T7") (pin "3") (pinfunction "C_3") (pintype "passive"))
      (node (ref "T8") (pin "3") (pinfunction "C_3") (pintype "passive"))
      (node (ref "U$1") (pin "VBUS") (pinfunction "VBUS_VBUS") (pintype "power_in"))
      (node (ref "U1") (pin "18") (pinfunction "AVCC_18") (pintype "bidirectional"))
      (node (ref "U1") (pin "20") (pinfunction "AREF_20") (pintype "bidirectional"))
      (node (ref "U1") (pin "4") (pinfunction "VCC_4") (pintype "bidirectional"))
      (node (ref "U1") (pin "6") (pinfunction "VCC_6") (pintype "bidirectional"))
    )
    (net (code "129") (name "unconnected-(IC6A-QH*-Pad9)") (class "Default")
      (node (ref "IC6") (pin "9") (pinfunction "QH*_9") (pintype "tri_state"))
    )
    (net (code "130") (name "unconnected-(SV7-Pad6)") (class "Default")
      (node (ref "SV7") (pin "6") (pinfunction "6_6") (pintype "passive"))
    )
    (net (code "131") (name "unconnected-(U1-ADC6-Pad19)") (class "Default")
      (node (ref "U1") (pin "19") (pinfunction "ADC6_19") (pintype "bidirectional"))
    )
    (net (code "132") (name "unconnected-(U1-ADC7-Pad22)") (class "Default")
      (node (ref "U1") (pin "22") (pinfunction "ADC7_22") (pintype "bidirectional"))
    )
    (net (code "133") (name "unconnected-(U1-PB1(OC1A)-Pad13)") (class "Default")
      (node (ref "U1") (pin "13") (pinfunction "PB1(OC1A)_13") (pintype "bidirectional"))
    )
    (net (code "134") (name "unconnected-(U1-PB2(SS{slash}OC1B)-Pad14)") (class "Default")
      (node (ref "U1") (pin "14") (pinfunction "PB2(SS/OC1B)_14") (pintype "bidirectional"))
    )
    (net (code "135") (name "unconnected-(U1-PC0(ADC0)-Pad23)") (class "Default")
      (node (ref "U1") (pin "23") (pinfunction "PC0(ADC0)_23") (pintype "bidirectional"))
    )
    (net (code "136") (name "unconnected-(U1-PC1(ADC1)-Pad24)") (class "Default")
      (node (ref "U1") (pin "24") (pinfunction "PC1(ADC1)_24") (pintype "bidirectional"))
    )
    (net (code "137") (name "unconnected-(U1-PC2(ADC2)-Pad25)") (class "Default")
      (node (ref "U1") (pin "25") (pinfunction "PC2(ADC2)_25") (pintype "bidirectional"))
    )
    (net (code "138") (name "unconnected-(U1-PC3(ADC3)-Pad26)") (class "Default")
      (node (ref "U1") (pin "26") (pinfunction "PC3(ADC3)_26") (pintype "bidirectional"))
    )
    (net (code "139") (name "unconnected-(U1-PC4(ADC4{slash}SDA)-Pad27)") (class "Default")
      (node (ref "U1") (pin "27") (pinfunction "PC4(ADC4/SDA)_27") (pintype "bidirectional"))
    )
    (net (code "140") (name "unconnected-(U1-PC5(ADC5{slash}SCL)-Pad28)") (class "Default")
      (node (ref "U1") (pin "28") (pinfunction "PC5(ADC5/SCL)_28") (pintype "bidirectional"))
    )
    (net (code "141") (name "unconnected-(U1-PD4(XCK{slash}T0)-Pad2)") (class "Default")
      (node (ref "U1") (pin "2") (pinfunction "PD4(XCK/T0)_2") (pintype "bidirectional"))
    )
    (net (code "142") (name "unconnected-(U1-PD7(AIN1)-Pad11)") (class "Default")
      (node (ref "U1") (pin "11") (pinfunction "PD7(AIN1)_11") (pintype "bidirectional"))
    )
  )
)
